# stackclock_display.net
KiCad netlist of a schematic drawn in EAGLE
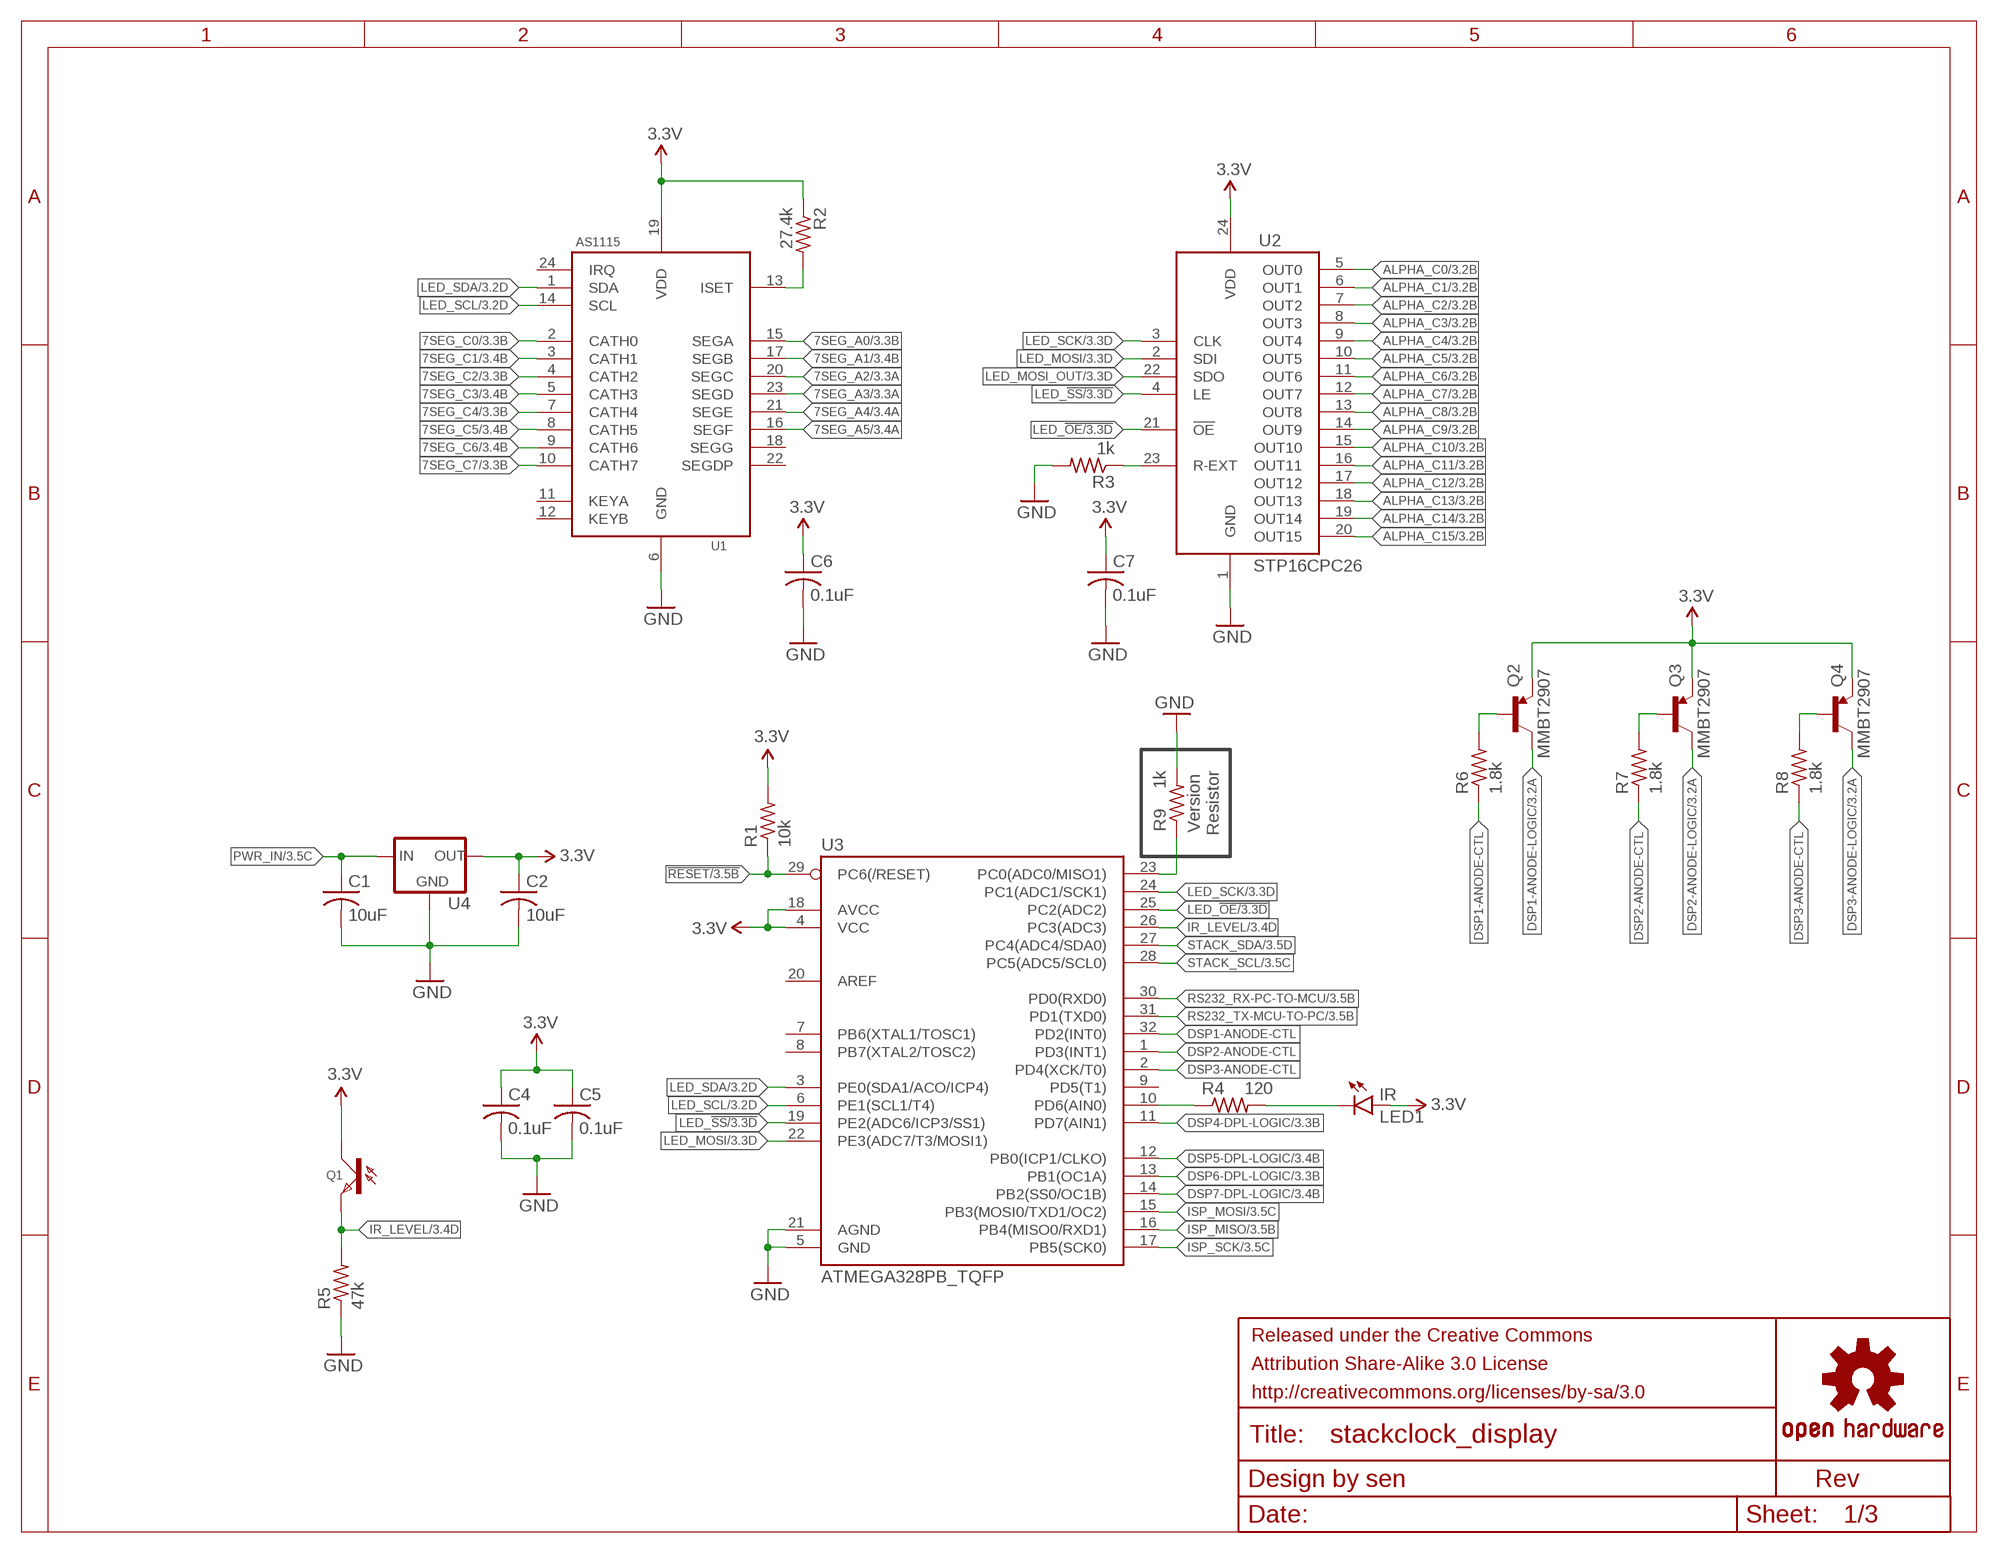
[diagram p0: schematic, sheet 1]
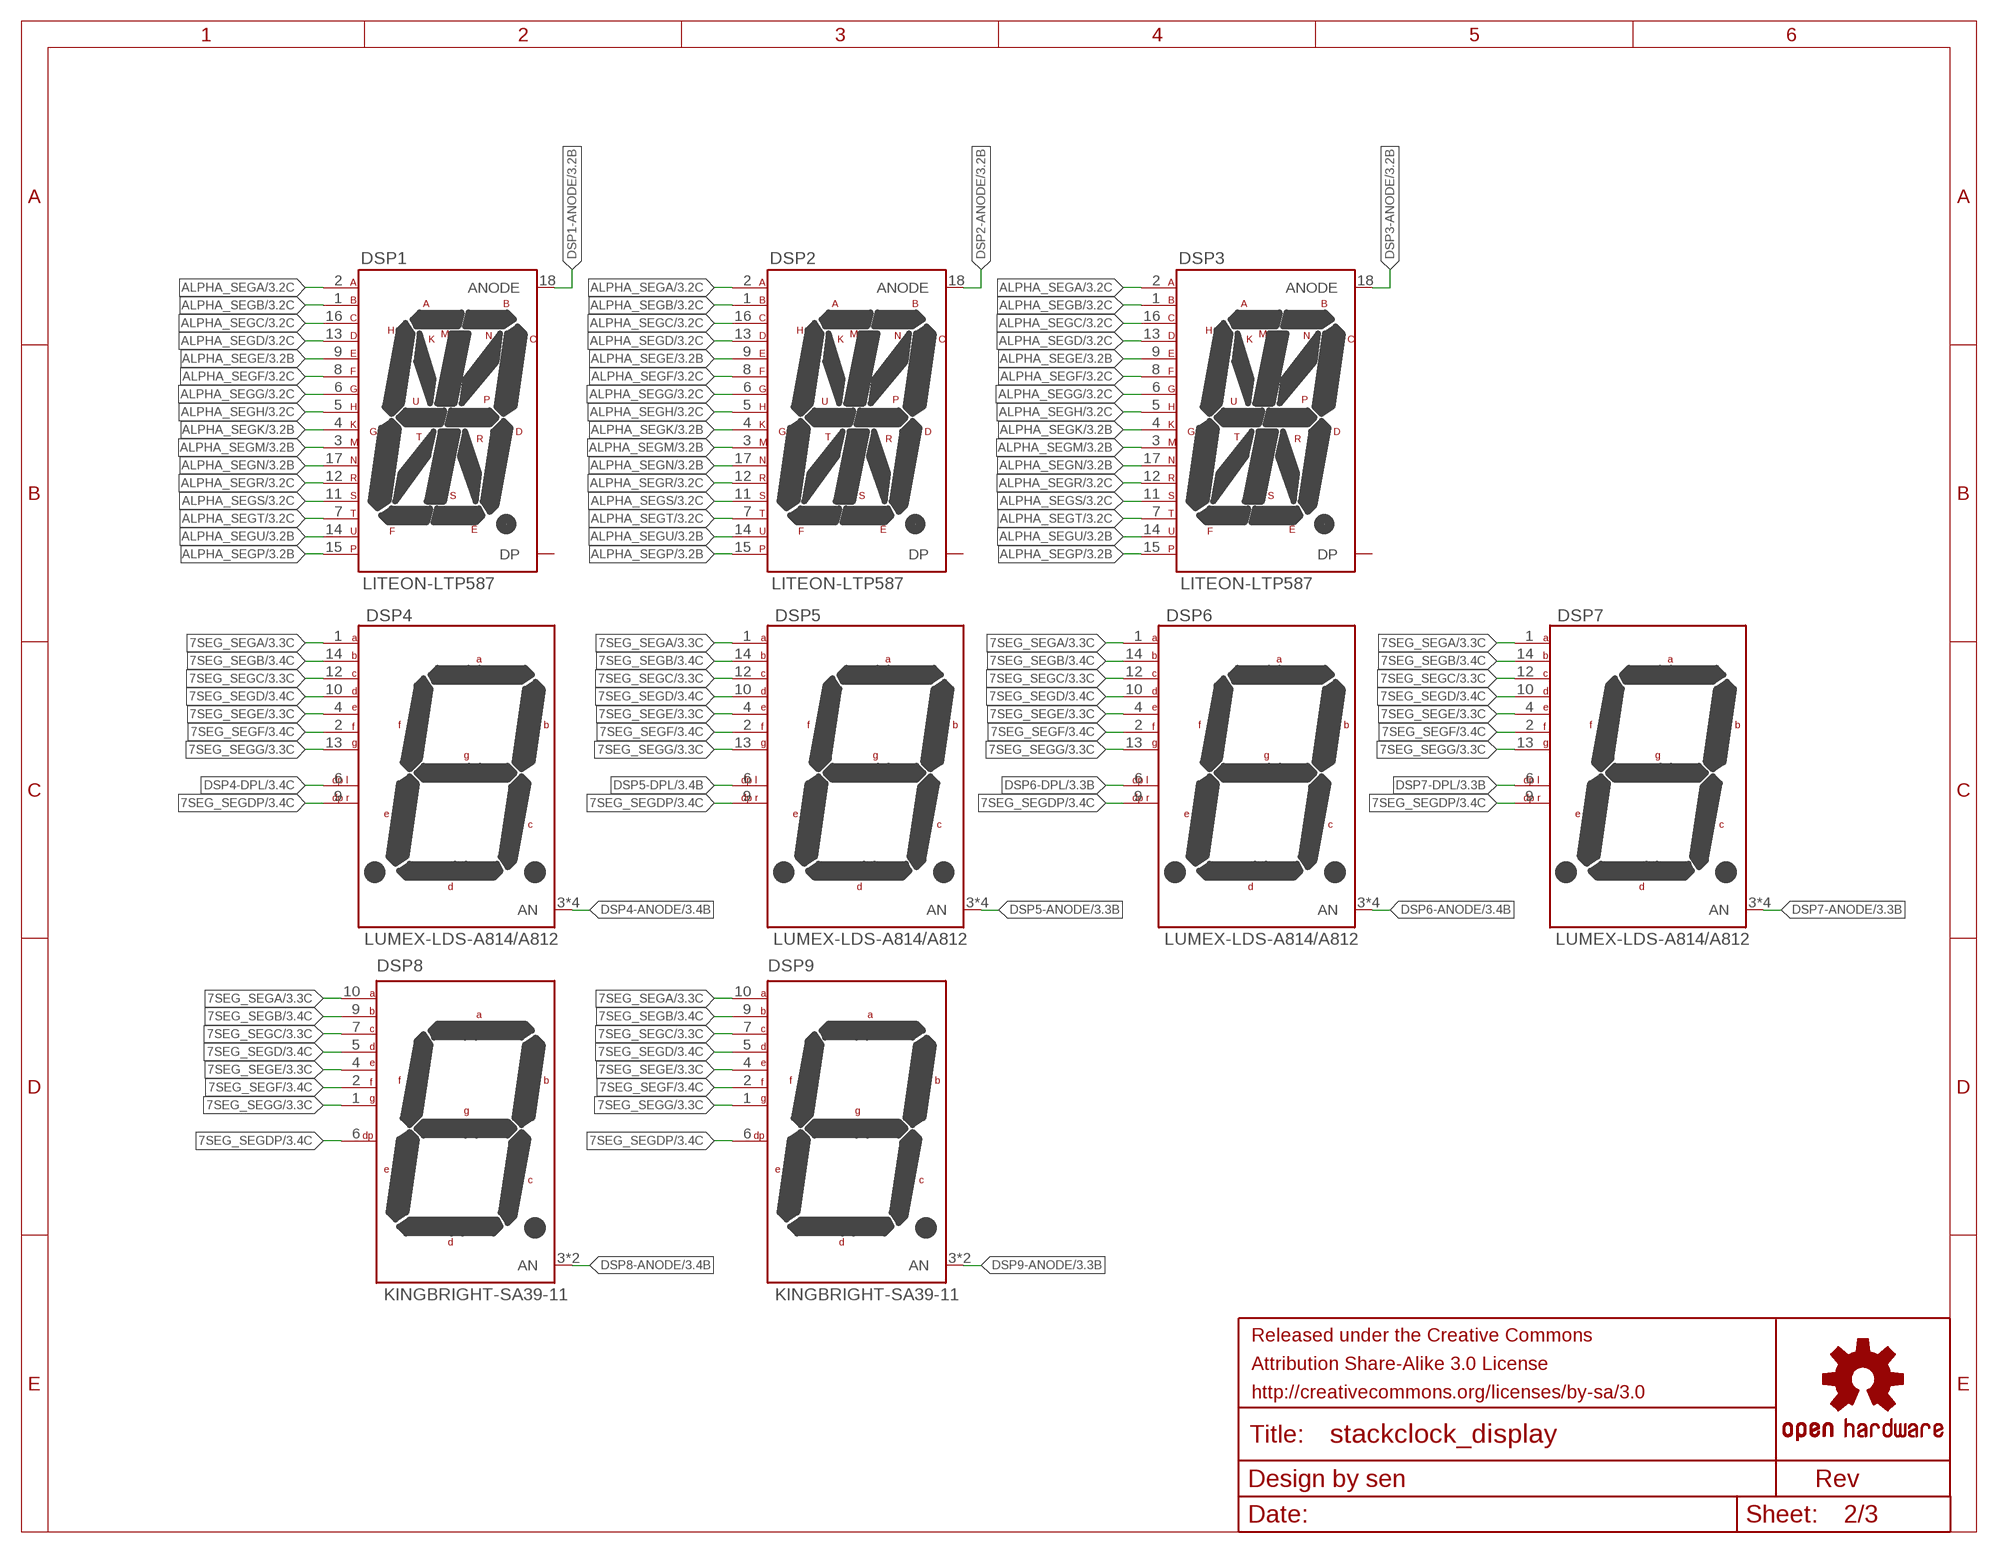
[diagram p1: schematic, sheet 2]
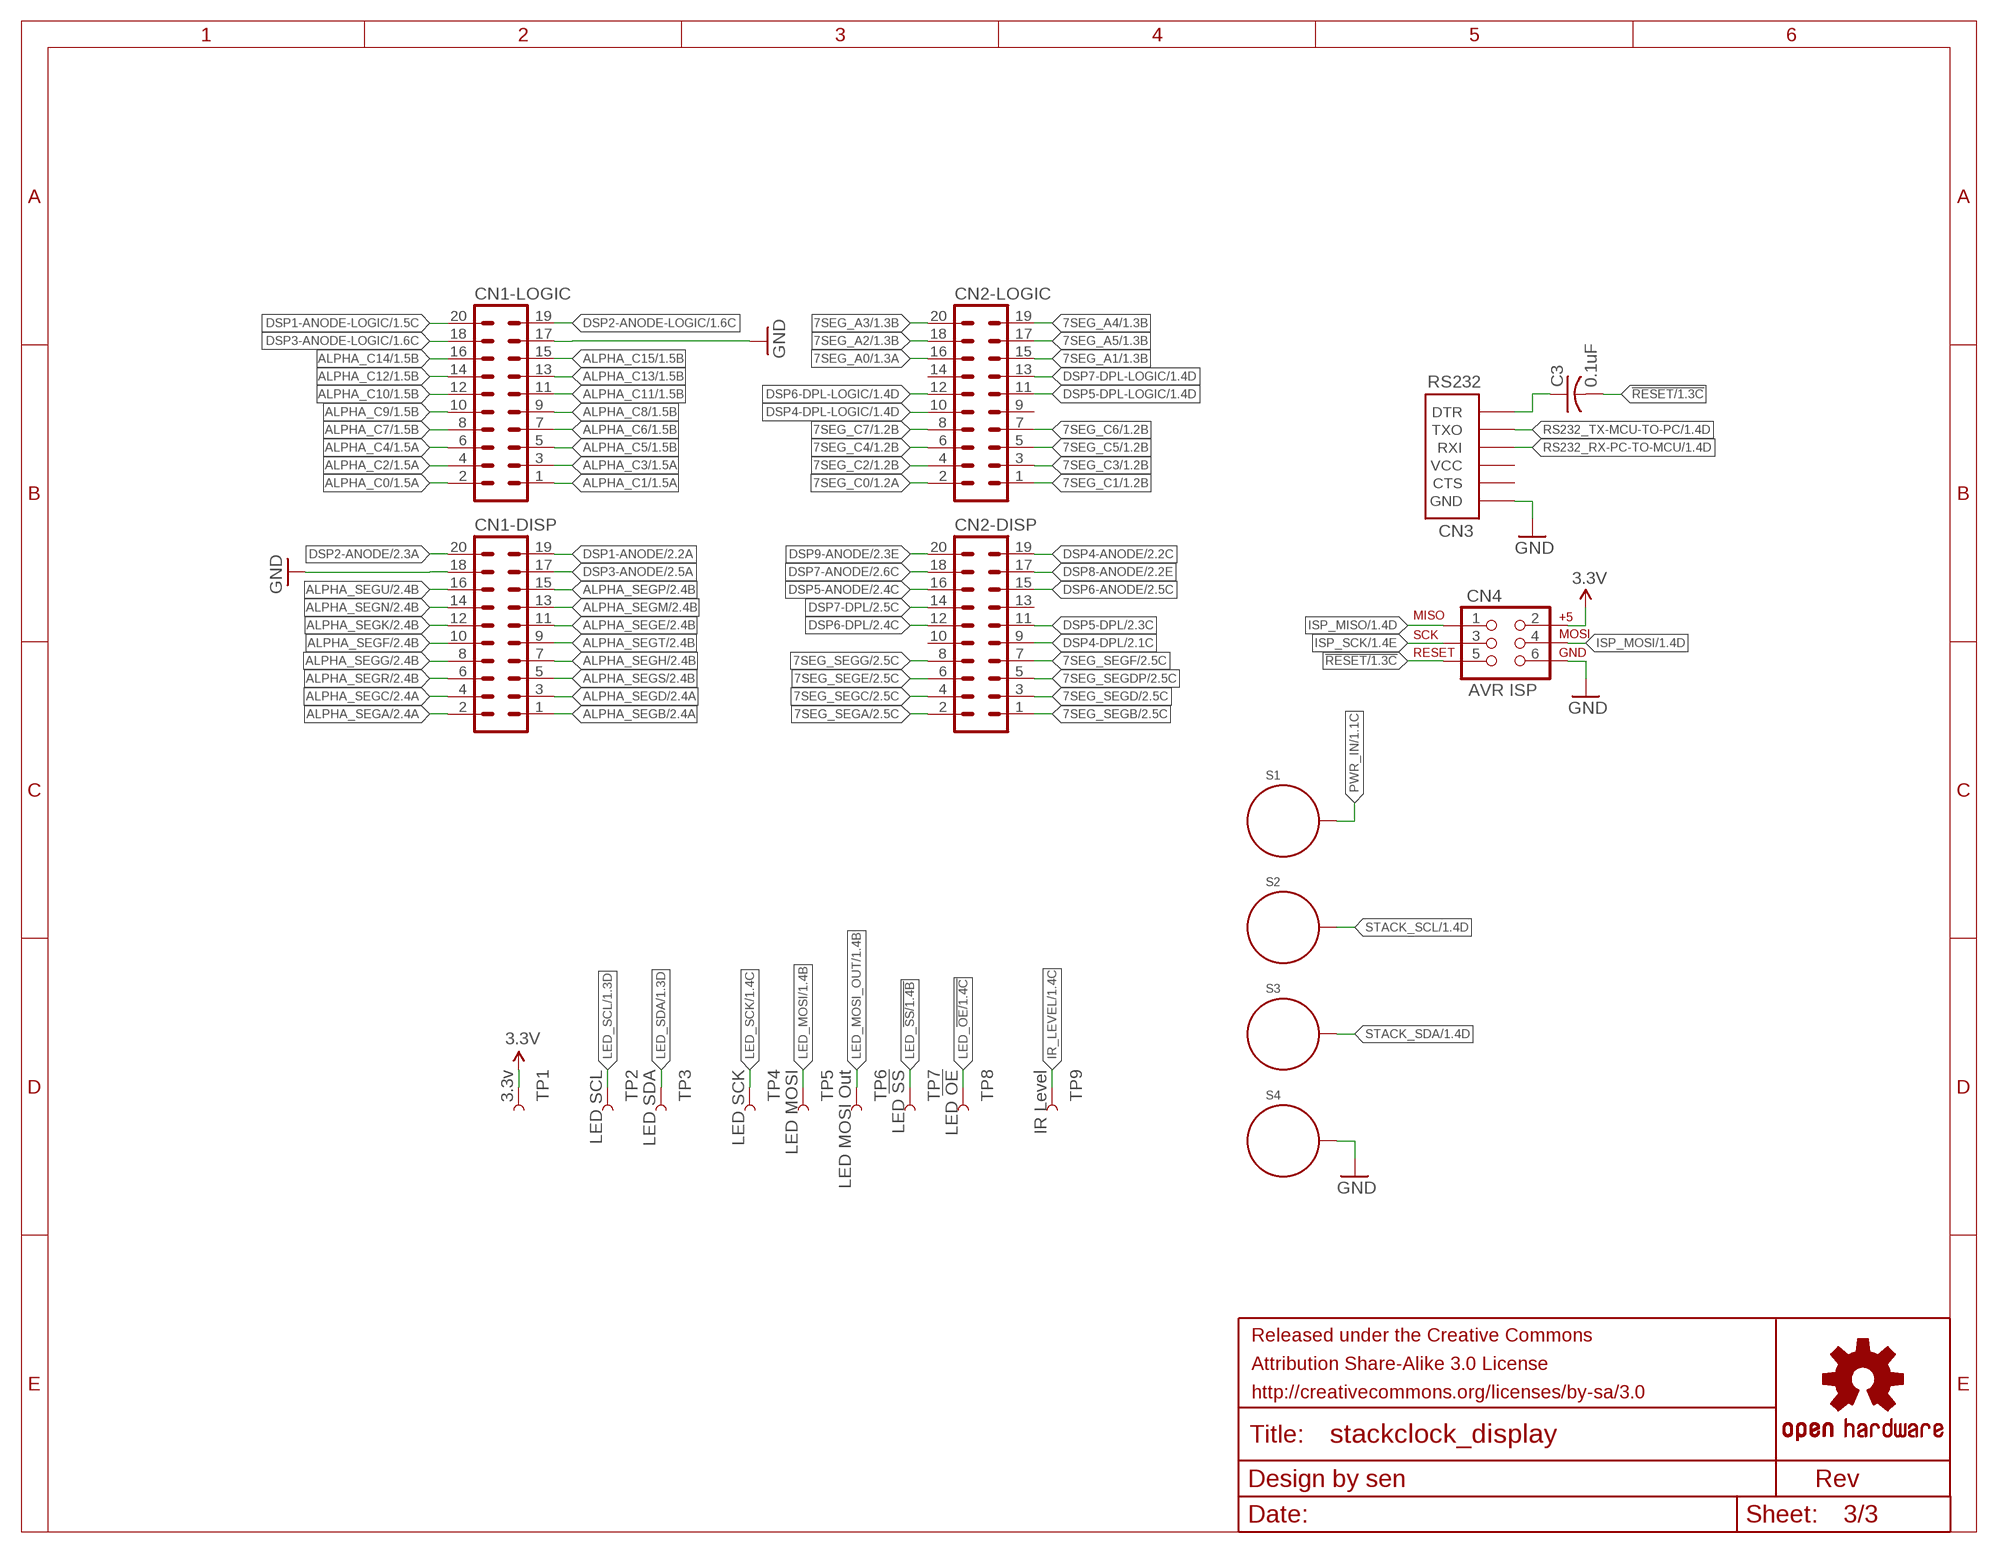
[diagram p2: schematic, sheet 3]

(export (version "E")
  (design (tool "Eeschema 10.0.6"))
  (components
    (comp (ref "DSP1")
      (value "LITEON-LTP587")
      (footprint "eagle-import:LITEON-LTP587")
      (libsource (lib "eagle-import") (part "LITEON-LTP587"))
    )
    (comp (ref "DSP2")
      (value "LITEON-LTP587")
      (footprint "eagle-import:LITEON-LTP587")
      (libsource (lib "eagle-import") (part "LITEON-LTP587"))
    )
    (comp (ref "DSP3")
      (value "LITEON-LTP587")
      (footprint "eagle-import:LITEON-LTP587")
      (libsource (lib "eagle-import") (part "LITEON-LTP587"))
    )
    (comp (ref "DSP4")
      (value "LUMEX-LDS-A814/A812")
      (footprint "eagle-import:LUMEX-LDS-A814_A812")
      (libsource (lib "eagle-import") (part "LUMEX-LDS-A814/A812"))
    )
    (comp (ref "DSP5")
      (value "LUMEX-LDS-A814/A812")
      (footprint "eagle-import:LUMEX-LDS-A814_A812")
      (libsource (lib "eagle-import") (part "LUMEX-LDS-A814/A812"))
    )
    (comp (ref "DSP6")
      (value "LUMEX-LDS-A814/A812")
      (footprint "eagle-import:LUMEX-LDS-A814_A812")
      (libsource (lib "eagle-import") (part "LUMEX-LDS-A814/A812"))
    )
    (comp (ref "DSP7")
      (value "LUMEX-LDS-A814/A812")
      (footprint "eagle-import:LUMEX-LDS-A814_A812")
      (libsource (lib "eagle-import") (part "LUMEX-LDS-A814/A812"))
    )
    (comp (ref "DSP8")
      (value "KINGBRIGHT-SA39-11")
      (footprint "eagle-import:KINGBRIGHT-SA39-11")
      (libsource (lib "eagle-import") (part "KINGBRIGHT-SA39-11"))
    )
    (comp (ref "DSP9")
      (value "KINGBRIGHT-SA39-11")
      (footprint "eagle-import:KINGBRIGHT-SA39-11")
      (libsource (lib "eagle-import") (part "KINGBRIGHT-SA39-11"))
    )
    (comp (ref "FRAME2")
      (value "FRAME-LETTER-GRID-OSHW-SENOSHW-LOGO-L")
      (footprint "eagle-import:OSHW-LOGO-L")
      (fields (field (name "REV") "002"))
      (libsource (lib "eagle-import") (part "FRAME-LETTER-GRID-OSHW-SENOSHW-LOGO-L"))
    )
    (comp (ref "C1")
      (value "10uF")
      (footprint "eagle-import:C0805")
      (libsource (lib "eagle-import") (part "C-USC0805"))
    )
    (comp (ref "C2")
      (value "10uF")
      (footprint "eagle-import:C0805")
      (libsource (lib "eagle-import") (part "C-USC0805"))
    )
    (comp (ref "C4")
      (value "0.1uF")
      (footprint "eagle-import:C0603")
      (libsource (lib "eagle-import") (part "C-USC0603"))
    )
    (comp (ref "C5")
      (value "0.1uF")
      (footprint "eagle-import:C0603")
      (libsource (lib "eagle-import") (part "C-USC0603"))
    )
    (comp (ref "C6")
      (value "0.1uF")
      (footprint "eagle-import:C0603")
      (libsource (lib "eagle-import") (part "C-USC0603"))
    )
    (comp (ref "C7")
      (value "0.1uF")
      (footprint "eagle-import:C0603")
      (libsource (lib "eagle-import") (part "C-USC0603"))
    )
    (comp (ref "FRAME1")
      (value "FRAME-LETTER-GRID-OSHW-SENOSHW-LOGO-L")
      (footprint "eagle-import:OSHW-LOGO-L")
      (fields (field (name "REV") "002"))
      (libsource (lib "eagle-import") (part "FRAME-LETTER-GRID-OSHW-SENOSHW-LOGO-L"))
    )
    (comp (ref "LED1")
      (value "IR")
      (footprint "eagle-import:LED-1206")
      (libsource (lib "eagle-import") (part "LED1206"))
    )
    (comp (ref "Q1")
      (value "PT15-21C/TR8")
      (footprint "eagle-import:1206_PHOTOTRANSISTOR")
      (libsource (lib "eagle-import") (part "PT15-21C/TR8"))
    )
    (comp (ref "Q2")
      (value "MMBT2907")
      (footprint "eagle-import:SOT23-3")
      (libsource (lib "eagle-import") (part "TRANSISTOR_PNPSMD"))
    )
    (comp (ref "Q3")
      (value "MMBT2907")
      (footprint "eagle-import:SOT23-3")
      (libsource (lib "eagle-import") (part "TRANSISTOR_PNPSMD"))
    )
    (comp (ref "Q4")
      (value "MMBT2907")
      (footprint "eagle-import:SOT23-3")
      (libsource (lib "eagle-import") (part "TRANSISTOR_PNPSMD"))
    )
    (comp (ref "R1")
      (value "10k")
      (footprint "eagle-import:R0603")
      (libsource (lib "eagle-import") (part "R-US_R0603"))
    )
    (comp (ref "R2")
      (value "27.4k")
      (footprint "eagle-import:R0603")
      (libsource (lib "eagle-import") (part "R-US_R0603"))
    )
    (comp (ref "R3")
      (value "1k")
      (footprint "eagle-import:R0603")
      (libsource (lib "eagle-import") (part "R-US_R0603"))
    )
    (comp (ref "R4")
      (value "120")
      (footprint "eagle-import:R0603")
      (libsource (lib "eagle-import") (part "R-US_R0603"))
    )
    (comp (ref "R5")
      (value "47k")
      (footprint "eagle-import:R0603")
      (libsource (lib "eagle-import") (part "R-US_R0603"))
    )
    (comp (ref "R6")
      (value "1.8k")
      (footprint "eagle-import:R0603")
      (libsource (lib "eagle-import") (part "R-US_R0603"))
    )
    (comp (ref "R7")
      (value "1.8k")
      (footprint "eagle-import:R0603")
      (libsource (lib "eagle-import") (part "R-US_R0603"))
    )
    (comp (ref "R8")
      (value "1.8k")
      (footprint "eagle-import:R0603")
      (libsource (lib "eagle-import") (part "R-US_R0603"))
    )
    (comp (ref "R9")
      (value "1k")
      (footprint "eagle-import:R0603")
      (libsource (lib "eagle-import") (part "R-US_R0603"))
    )
    (comp (ref "U1")
      (value "AS1115")
      (footprint "eagle-import:QSOP24")
      (libsource (lib "eagle-import") (part "AS1115"))
    )
    (comp (ref "U2")
      (value "STP16CPC26")
      (footprint "eagle-import:TSSOP24")
      (libsource (lib "eagle-import") (part "STP16CPC26"))
    )
    (comp (ref "U3")
      (value "ATMEGA328PB_TQFP")
      (footprint "eagle-import:TQFP32-08")
      (libsource (lib "eagle-import") (part "ATMEGA328PB_TQFP"))
    )
    (comp (ref "U4")
      (value "NCP1117DT33G")
      (footprint "eagle-import:DPAK")
      (libsource (lib "eagle-import") (part "V_REG_MC33269DT"))
    )
    (comp (ref "C3")
      (value "0.1uF")
      (footprint "eagle-import:C0603")
      (libsource (lib "eagle-import") (part "C-USC0603"))
    )
    (comp (ref "CN1-DISP")
      (value "MA10-2W")
      (footprint "eagle-import:MA10-2W")
      (libsource (lib "eagle-import") (part "MA10-2W"))
    )
    (comp (ref "CN1-LOGIC")
      (value "MA10-2")
      (footprint "eagle-import:MA10-2")
      (libsource (lib "eagle-import") (part "MA10-2"))
    )
    (comp (ref "CN2-DISP")
      (value "MA10-2W")
      (footprint "eagle-import:MA10-2W")
      (libsource (lib "eagle-import") (part "MA10-2W"))
    )
    (comp (ref "CN2-LOGIC")
      (value "MA10-2")
      (footprint "eagle-import:MA10-2")
      (libsource (lib "eagle-import") (part "MA10-2"))
    )
    (comp (ref "CN3")
      (value "RS232")
      (footprint "eagle-import:FTDI_DEVICE_SIDE")
      (libsource (lib "eagle-import") (part "FTDI_DEVICE"))
    )
    (comp (ref "CN4")
      (value "AVR ISP")
      (footprint "eagle-import:2X3_LOCK")
      (libsource (lib "eagle-import") (part "AVR_SPI_PRG_62X3_LOCK"))
    )
    (comp (ref "FRAME3")
      (value "FRAME-LETTER-GRID-OSHW-SENOSHW-LOGO-L")
      (footprint "eagle-import:OSHW-LOGO-L")
      (fields (field (name "REV") "002"))
      (libsource (lib "eagle-import") (part "FRAME-LETTER-GRID-OSHW-SENOSHW-LOGO-L"))
    )
    (comp (ref "S1")
      (value "+V")
      (footprint "eagle-import:STANDOFF-ELECTRICAL")
      (libsource (lib "eagle-import") (part "STANDOFF_ELECTRICAL"))
    )
    (comp (ref "S2")
      (value "SCL")
      (footprint "eagle-import:STANDOFF-ELECTRICAL")
      (libsource (lib "eagle-import") (part "STANDOFF_ELECTRICAL"))
    )
    (comp (ref "S3")
      (value "SDA")
      (footprint "eagle-import:STANDOFF-ELECTRICAL")
      (libsource (lib "eagle-import") (part "STANDOFF_ELECTRICAL"))
    )
    (comp (ref "S4")
      (value "GND")
      (footprint "eagle-import:STANDOFF-ELECTRICAL")
      (libsource (lib "eagle-import") (part "STANDOFF_ELECTRICAL"))
    )
    (comp (ref "TP1")
      (value "3.3v")
      (footprint "eagle-import:TP_15TH")
      (libsource (lib "eagle-import") (part "TEST-POINTTP_15TH_THRU"))
    )
    (comp (ref "TP2")
      (value "LED SCL")
      (footprint "eagle-import:TP_15TH")
      (libsource (lib "eagle-import") (part "TEST-POINTTP_15TH_THRU"))
    )
    (comp (ref "TP3")
      (value "LED SDA")
      (footprint "eagle-import:TP_15TH")
      (libsource (lib "eagle-import") (part "TEST-POINTTP_15TH_THRU"))
    )
    (comp (ref "TP4")
      (value "LED SCK")
      (footprint "eagle-import:TP_15TH")
      (libsource (lib "eagle-import") (part "TEST-POINTTP_15TH_THRU"))
    )
    (comp (ref "TP5")
      (value "LED MOSI")
      (footprint "eagle-import:TP_15TH")
      (libsource (lib "eagle-import") (part "TEST-POINTTP_15TH_THRU"))
    )
    (comp (ref "TP6")
      (value "LED MOSI Out")
      (footprint "eagle-import:TP_15TH")
      (libsource (lib "eagle-import") (part "TEST-POINTTP_15TH_THRU"))
    )
    (comp (ref "TP7")
      (value "LED !SS")
      (footprint "eagle-import:TP_15TH")
      (libsource (lib "eagle-import") (part "TEST-POINTTP_15TH_THRU"))
    )
    (comp (ref "TP8")
      (value "LED !OE")
      (footprint "eagle-import:TP_15TH")
      (libsource (lib "eagle-import") (part "TEST-POINTTP_15TH_THRU"))
    )
    (comp (ref "TP9")
      (value "IR Level")
      (footprint "eagle-import:TP_15TH")
      (libsource (lib "eagle-import") (part "TEST-POINTTP_15TH_THRU"))
    )
  )
  (nets
    (net (code "1") (name "3.3V") (class "Default")
      (node (ref "C2") (pin "1") (pinfunction "1_1") (pintype "passive"))
      (node (ref "C4") (pin "1") (pinfunction "1_1") (pintype "passive"))
      (node (ref "C5") (pin "1") (pinfunction "1_1") (pintype "passive"))
      (node (ref "C6") (pin "1") (pinfunction "1_1") (pintype "passive"))
      (node (ref "C7") (pin "1") (pinfunction "1_1") (pintype "passive"))
      (node (ref "CN4") (pin "2") (pinfunction "2_2") (pintype "passive"))
      (node (ref "LED1") (pin "A") (pinfunction "A_A") (pintype "passive"))
      (node (ref "Q1") (pin "C") (pinfunction "C_C") (pintype "passive"))
      (node (ref "Q2") (pin "2") (pinfunction "E_2") (pintype "passive"))
      (node (ref "Q3") (pin "2") (pinfunction "E_2") (pintype "passive"))
      (node (ref "Q4") (pin "2") (pinfunction "E_2") (pintype "passive"))
      (node (ref "R1") (pin "2") (pinfunction "2_2") (pintype "passive"))
      (node (ref "R2") (pin "1") (pinfunction "1_1") (pintype "passive"))
      (node (ref "TP1") (pin "P$1") (pinfunction "1_P$1") (pintype "bidirectional"))
      (node (ref "U1") (pin "19") (pinfunction "VDD_19") (pintype "power_in"))
      (node (ref "U2") (pin "24") (pinfunction "VDD_24") (pintype "bidirectional"))
      (node (ref "U3") (pin "18") (pinfunction "AVCC_18") (pintype "bidirectional"))
      (node (ref "U3") (pin "4") (pinfunction "VCC_4") (pintype "bidirectional"))
      (node (ref "U4") (pin "4") (pinfunction "OUT_4") (pintype "passive"))
    )
    (net (code "2") (name "7SEG_A0") (class "Default")
      (node (ref "CN2-LOGIC") (pin "16") (pinfunction "16_16") (pintype "passive"))
      (node (ref "U1") (pin "15") (pinfunction "SEGA_15") (pintype "output"))
    )
    (net (code "3") (name "7SEG_A1") (class "Default")
      (node (ref "CN2-LOGIC") (pin "15") (pinfunction "15_15") (pintype "passive"))
      (node (ref "U1") (pin "17") (pinfunction "SEGB_17") (pintype "output"))
    )
    (net (code "4") (name "7SEG_A2") (class "Default")
      (node (ref "CN2-LOGIC") (pin "18") (pinfunction "18_18") (pintype "passive"))
      (node (ref "U1") (pin "20") (pinfunction "SEGC_20") (pintype "output"))
    )
    (net (code "5") (name "7SEG_A3") (class "Default")
      (node (ref "CN2-LOGIC") (pin "20") (pinfunction "20_20") (pintype "passive"))
      (node (ref "U1") (pin "23") (pinfunction "SEGD_23") (pintype "output"))
    )
    (net (code "6") (name "7SEG_A4") (class "Default")
      (node (ref "CN2-LOGIC") (pin "19") (pinfunction "19_19") (pintype "passive"))
      (node (ref "U1") (pin "21") (pinfunction "SEGE_21") (pintype "output"))
    )
    (net (code "7") (name "7SEG_A5") (class "Default")
      (node (ref "CN2-LOGIC") (pin "17") (pinfunction "17_17") (pintype "passive"))
      (node (ref "U1") (pin "16") (pinfunction "SEGF_16") (pintype "output"))
    )
    (net (code "8") (name "7SEG_C0") (class "Default")
      (node (ref "CN2-LOGIC") (pin "2") (pinfunction "2_2") (pintype "passive"))
      (node (ref "U1") (pin "2") (pinfunction "CATH0_2") (pintype "output"))
    )
    (net (code "9") (name "7SEG_C1") (class "Default")
      (node (ref "CN2-LOGIC") (pin "1") (pinfunction "1_1") (pintype "passive"))
      (node (ref "U1") (pin "3") (pinfunction "CATH1_3") (pintype "output"))
    )
    (net (code "10") (name "7SEG_C2") (class "Default")
      (node (ref "CN2-LOGIC") (pin "4") (pinfunction "4_4") (pintype "passive"))
      (node (ref "U1") (pin "4") (pinfunction "CATH2_4") (pintype "output"))
    )
    (net (code "11") (name "7SEG_C3") (class "Default")
      (node (ref "CN2-LOGIC") (pin "3") (pinfunction "3_3") (pintype "passive"))
      (node (ref "U1") (pin "5") (pinfunction "CATH3_5") (pintype "output"))
    )
    (net (code "12") (name "7SEG_C4") (class "Default")
      (node (ref "CN2-LOGIC") (pin "6") (pinfunction "6_6") (pintype "passive"))
      (node (ref "U1") (pin "7") (pinfunction "CATH4_7") (pintype "output"))
    )
    (net (code "13") (name "7SEG_C5") (class "Default")
      (node (ref "CN2-LOGIC") (pin "5") (pinfunction "5_5") (pintype "passive"))
      (node (ref "U1") (pin "8") (pinfunction "CATH5_8") (pintype "output"))
    )
    (net (code "14") (name "7SEG_C6") (class "Default")
      (node (ref "CN2-LOGIC") (pin "7") (pinfunction "7_7") (pintype "passive"))
      (node (ref "U1") (pin "9") (pinfunction "CATH6_9") (pintype "output"))
    )
    (net (code "15") (name "7SEG_C7") (class "Default")
      (node (ref "CN2-LOGIC") (pin "8") (pinfunction "8_8") (pintype "passive"))
      (node (ref "U1") (pin "10") (pinfunction "CATH7_10") (pintype "output"))
    )
    (net (code "16") (name "7SEG_SEGA") (class "Default")
      (node (ref "CN2-DISP") (pin "2") (pinfunction "2_2") (pintype "passive"))
      (node (ref "DSP4") (pin "1") (pinfunction "A_1") (pintype "passive"))
      (node (ref "DSP5") (pin "1") (pinfunction "A_1") (pintype "passive"))
      (node (ref "DSP6") (pin "1") (pinfunction "A_1") (pintype "passive"))
      (node (ref "DSP7") (pin "1") (pinfunction "A_1") (pintype "passive"))
      (node (ref "DSP8") (pin "10") (pinfunction "A_10") (pintype "passive"))
      (node (ref "DSP9") (pin "10") (pinfunction "A_10") (pintype "passive"))
    )
    (net (code "17") (name "7SEG_SEGB") (class "Default")
      (node (ref "CN2-DISP") (pin "1") (pinfunction "1_1") (pintype "passive"))
      (node (ref "DSP4") (pin "14") (pinfunction "B_14") (pintype "passive"))
      (node (ref "DSP5") (pin "14") (pinfunction "B_14") (pintype "passive"))
      (node (ref "DSP6") (pin "14") (pinfunction "B_14") (pintype "passive"))
      (node (ref "DSP7") (pin "14") (pinfunction "B_14") (pintype "passive"))
      (node (ref "DSP8") (pin "9") (pinfunction "B_9") (pintype "passive"))
      (node (ref "DSP9") (pin "9") (pinfunction "B_9") (pintype "passive"))
    )
    (net (code "18") (name "7SEG_SEGC") (class "Default")
      (node (ref "CN2-DISP") (pin "4") (pinfunction "4_4") (pintype "passive"))
      (node (ref "DSP4") (pin "12") (pinfunction "C_12") (pintype "passive"))
      (node (ref "DSP5") (pin "12") (pinfunction "C_12") (pintype "passive"))
      (node (ref "DSP6") (pin "12") (pinfunction "C_12") (pintype "passive"))
      (node (ref "DSP7") (pin "12") (pinfunction "C_12") (pintype "passive"))
      (node (ref "DSP8") (pin "7") (pinfunction "C_7") (pintype "passive"))
      (node (ref "DSP9") (pin "7") (pinfunction "C_7") (pintype "passive"))
    )
    (net (code "19") (name "7SEG_SEGD") (class "Default")
      (node (ref "CN2-DISP") (pin "3") (pinfunction "3_3") (pintype "passive"))
      (node (ref "DSP4") (pin "10") (pinfunction "D_10") (pintype "passive"))
      (node (ref "DSP5") (pin "10") (pinfunction "D_10") (pintype "passive"))
      (node (ref "DSP6") (pin "10") (pinfunction "D_10") (pintype "passive"))
      (node (ref "DSP7") (pin "10") (pinfunction "D_10") (pintype "passive"))
      (node (ref "DSP8") (pin "5") (pinfunction "D_5") (pintype "passive"))
      (node (ref "DSP9") (pin "5") (pinfunction "D_5") (pintype "passive"))
    )
    (net (code "20") (name "7SEG_SEGDP") (class "Default")
      (node (ref "CN2-DISP") (pin "5") (pinfunction "5_5") (pintype "passive"))
      (node (ref "DSP4") (pin "9") (pinfunction "DP-R_9") (pintype "passive"))
      (node (ref "DSP5") (pin "9") (pinfunction "DP-R_9") (pintype "passive"))
      (node (ref "DSP6") (pin "9") (pinfunction "DP-R_9") (pintype "passive"))
      (node (ref "DSP7") (pin "9") (pinfunction "DP-R_9") (pintype "passive"))
      (node (ref "DSP8") (pin "6") (pinfunction "DP_6") (pintype "passive"))
      (node (ref "DSP9") (pin "6") (pinfunction "DP_6") (pintype "passive"))
    )
    (net (code "21") (name "7SEG_SEGE") (class "Default")
      (node (ref "CN2-DISP") (pin "6") (pinfunction "6_6") (pintype "passive"))
      (node (ref "DSP4") (pin "4") (pinfunction "E_4") (pintype "passive"))
      (node (ref "DSP5") (pin "4") (pinfunction "E_4") (pintype "passive"))
      (node (ref "DSP6") (pin "4") (pinfunction "E_4") (pintype "passive"))
      (node (ref "DSP7") (pin "4") (pinfunction "E_4") (pintype "passive"))
      (node (ref "DSP8") (pin "4") (pinfunction "E_4") (pintype "passive"))
      (node (ref "DSP9") (pin "4") (pinfunction "E_4") (pintype "passive"))
    )
    (net (code "22") (name "7SEG_SEGF") (class "Default")
      (node (ref "CN2-DISP") (pin "7") (pinfunction "7_7") (pintype "passive"))
      (node (ref "DSP4") (pin "2") (pinfunction "F_2") (pintype "passive"))
      (node (ref "DSP5") (pin "2") (pinfunction "F_2") (pintype "passive"))
      (node (ref "DSP6") (pin "2") (pinfunction "F_2") (pintype "passive"))
      (node (ref "DSP7") (pin "2") (pinfunction "F_2") (pintype "passive"))
      (node (ref "DSP8") (pin "2") (pinfunction "F_2") (pintype "passive"))
      (node (ref "DSP9") (pin "2") (pinfunction "F_2") (pintype "passive"))
    )
    (net (code "23") (name "7SEG_SEGG") (class "Default")
      (node (ref "CN2-DISP") (pin "8") (pinfunction "8_8") (pintype "passive"))
      (node (ref "DSP4") (pin "13") (pinfunction "G_13") (pintype "passive"))
      (node (ref "DSP5") (pin "13") (pinfunction "G_13") (pintype "passive"))
      (node (ref "DSP6") (pin "13") (pinfunction "G_13") (pintype "passive"))
      (node (ref "DSP7") (pin "13") (pinfunction "G_13") (pintype "passive"))
      (node (ref "DSP8") (pin "1") (pinfunction "G_1") (pintype "passive"))
      (node (ref "DSP9") (pin "1") (pinfunction "G_1") (pintype "passive"))
    )
    (net (code "24") (name "ALPHA_C0") (class "Default")
      (node (ref "CN1-LOGIC") (pin "2") (pinfunction "2_2") (pintype "passive"))
      (node (ref "U2") (pin "5") (pinfunction "OUT0_5") (pintype "output"))
    )
    (net (code "25") (name "ALPHA_C1") (class "Default")
      (node (ref "CN1-LOGIC") (pin "1") (pinfunction "1_1") (pintype "passive"))
      (node (ref "U2") (pin "6") (pinfunction "OUT1_6") (pintype "output"))
    )
    (net (code "26") (name "ALPHA_C2") (class "Default")
      (node (ref "CN1-LOGIC") (pin "4") (pinfunction "4_4") (pintype "passive"))
      (node (ref "U2") (pin "7") (pinfunction "OUT2_7") (pintype "output"))
    )
    (net (code "27") (name "ALPHA_C3") (class "Default")
      (node (ref "CN1-LOGIC") (pin "3") (pinfunction "3_3") (pintype "passive"))
      (node (ref "U2") (pin "8") (pinfunction "OUT3_8") (pintype "output"))
    )
    (net (code "28") (name "ALPHA_C4") (class "Default")
      (node (ref "CN1-LOGIC") (pin "6") (pinfunction "6_6") (pintype "passive"))
      (node (ref "U2") (pin "9") (pinfunction "OUT4_9") (pintype "output"))
    )
    (net (code "29") (name "ALPHA_C5") (class "Default")
      (node (ref "CN1-LOGIC") (pin "5") (pinfunction "5_5") (pintype "passive"))
      (node (ref "U2") (pin "10") (pinfunction "OUT5_10") (pintype "output"))
    )
    (net (code "30") (name "ALPHA_C6") (class "Default")
      (node (ref "CN1-LOGIC") (pin "7") (pinfunction "7_7") (pintype "passive"))
      (node (ref "U2") (pin "11") (pinfunction "OUT6_11") (pintype "output"))
    )
    (net (code "31") (name "ALPHA_C7") (class "Default")
      (node (ref "CN1-LOGIC") (pin "8") (pinfunction "8_8") (pintype "passive"))
      (node (ref "U2") (pin "12") (pinfunction "OUT7_12") (pintype "output"))
    )
    (net (code "32") (name "ALPHA_C8") (class "Default")
      (node (ref "CN1-LOGIC") (pin "9") (pinfunction "9_9") (pintype "passive"))
      (node (ref "U2") (pin "13") (pinfunction "OUT8_13") (pintype "output"))
    )
    (net (code "33") (name "ALPHA_C9") (class "Default")
      (node (ref "CN1-LOGIC") (pin "10") (pinfunction "10_10") (pintype "passive"))
      (node (ref "U2") (pin "14") (pinfunction "OUT9_14") (pintype "output"))
    )
    (net (code "34") (name "ALPHA_C10") (class "Default")
      (node (ref "CN1-LOGIC") (pin "12") (pinfunction "12_12") (pintype "passive"))
      (node (ref "U2") (pin "15") (pinfunction "OUT10_15") (pintype "output"))
    )
    (net (code "35") (name "ALPHA_C11") (class "Default")
      (node (ref "CN1-LOGIC") (pin "11") (pinfunction "11_11") (pintype "passive"))
      (node (ref "U2") (pin "16") (pinfunction "OUT11_16") (pintype "output"))
    )
    (net (code "36") (name "ALPHA_C12") (class "Default")
      (node (ref "CN1-LOGIC") (pin "14") (pinfunction "14_14") (pintype "passive"))
      (node (ref "U2") (pin "17") (pinfunction "OUT12_17") (pintype "output"))
    )
    (net (code "37") (name "ALPHA_C13") (class "Default")
      (node (ref "CN1-LOGIC") (pin "13") (pinfunction "13_13") (pintype "passive"))
      (node (ref "U2") (pin "18") (pinfunction "OUT13_18") (pintype "output"))
    )
    (net (code "38") (name "ALPHA_C14") (class "Default")
      (node (ref "CN1-LOGIC") (pin "16") (pinfunction "16_16") (pintype "passive"))
      (node (ref "U2") (pin "19") (pinfunction "OUT14_19") (pintype "output"))
    )
    (net (code "39") (name "ALPHA_C15") (class "Default")
      (node (ref "CN1-LOGIC") (pin "15") (pinfunction "15_15") (pintype "passive"))
      (node (ref "U2") (pin "20") (pinfunction "OUT15_20") (pintype "output"))
    )
    (net (code "40") (name "ALPHA_SEGA") (class "Default")
      (node (ref "CN1-DISP") (pin "2") (pinfunction "2_2") (pintype "passive"))
      (node (ref "DSP1") (pin "2") (pinfunction "A_2") (pintype "passive"))
      (node (ref "DSP2") (pin "2") (pinfunction "A_2") (pintype "passive"))
      (node (ref "DSP3") (pin "2") (pinfunction "A_2") (pintype "passive"))
    )
    (net (code "41") (name "ALPHA_SEGB") (class "Default")
      (node (ref "CN1-DISP") (pin "1") (pinfunction "1_1") (pintype "passive"))
      (node (ref "DSP1") (pin "1") (pinfunction "B_1") (pintype "passive"))
      (node (ref "DSP2") (pin "1") (pinfunction "B_1") (pintype "passive"))
      (node (ref "DSP3") (pin "1") (pinfunction "B_1") (pintype "passive"))
    )
    (net (code "42") (name "ALPHA_SEGC") (class "Default")
      (node (ref "CN1-DISP") (pin "4") (pinfunction "4_4") (pintype "passive"))
      (node (ref "DSP1") (pin "16") (pinfunction "C_16") (pintype "passive"))
      (node (ref "DSP2") (pin "16") (pinfunction "C_16") (pintype "passive"))
      (node (ref "DSP3") (pin "16") (pinfunction "C_16") (pintype "passive"))
    )
    (net (code "43") (name "ALPHA_SEGD") (class "Default")
      (node (ref "CN1-DISP") (pin "3") (pinfunction "3_3") (pintype "passive"))
      (node (ref "DSP1") (pin "13") (pinfunction "D_13") (pintype "passive"))
      (node (ref "DSP2") (pin "13") (pinfunction "D_13") (pintype "passive"))
      (node (ref "DSP3") (pin "13") (pinfunction "D_13") (pintype "passive"))
    )
    (net (code "44") (name "ALPHA_SEGE") (class "Default")
      (node (ref "CN1-DISP") (pin "11") (pinfunction "11_11") (pintype "passive"))
      (node (ref "DSP1") (pin "9") (pinfunction "E_9") (pintype "passive"))
      (node (ref "DSP2") (pin "9") (pinfunction "E_9") (pintype "passive"))
      (node (ref "DSP3") (pin "9") (pinfunction "E_9") (pintype "passive"))
    )
    (net (code "45") (name "ALPHA_SEGF") (class "Default")
      (node (ref "CN1-DISP") (pin "10") (pinfunction "10_10") (pintype "passive"))
      (node (ref "DSP1") (pin "8") (pinfunction "F_8") (pintype "passive"))
      (node (ref "DSP2") (pin "8") (pinfunction "F_8") (pintype "passive"))
      (node (ref "DSP3") (pin "8") (pinfunction "F_8") (pintype "passive"))
    )
    (net (code "46") (name "ALPHA_SEGG") (class "Default")
      (node (ref "CN1-DISP") (pin "8") (pinfunction "8_8") (pintype "passive"))
      (node (ref "DSP1") (pin "6") (pinfunction "G_6") (pintype "passive"))
      (node (ref "DSP2") (pin "6") (pinfunction "G_6") (pintype "passive"))
      (node (ref "DSP3") (pin "6") (pinfunction "G_6") (pintype "passive"))
    )
    (net (code "47") (name "ALPHA_SEGH") (class "Default")
      (node (ref "CN1-DISP") (pin "7") (pinfunction "7_7") (pintype "passive"))
      (node (ref "DSP1") (pin "5") (pinfunction "H_5") (pintype "passive"))
      (node (ref "DSP2") (pin "5") (pinfunction "H_5") (pintype "passive"))
      (node (ref "DSP3") (pin "5") (pinfunction "H_5") (pintype "passive"))
    )
    (net (code "48") (name "ALPHA_SEGK") (class "Default")
      (node (ref "CN1-DISP") (pin "12") (pinfunction "12_12") (pintype "passive"))
      (node (ref "DSP1") (pin "4") (pinfunction "K_4") (pintype "passive"))
      (node (ref "DSP2") (pin "4") (pinfunction "K_4") (pintype "passive"))
      (node (ref "DSP3") (pin "4") (pinfunction "K_4") (pintype "passive"))
    )
    (net (code "49") (name "ALPHA_SEGM") (class "Default")
      (node (ref "CN1-DISP") (pin "13") (pinfunction "13_13") (pintype "passive"))
      (node (ref "DSP1") (pin "3") (pinfunction "M_3") (pintype "passive"))
      (node (ref "DSP2") (pin "3") (pinfunction "M_3") (pintype "passive"))
      (node (ref "DSP3") (pin "3") (pinfunction "M_3") (pintype "passive"))
    )
    (net (code "50") (name "ALPHA_SEGN") (class "Default")
      (node (ref "CN1-DISP") (pin "14") (pinfunction "14_14") (pintype "passive"))
      (node (ref "DSP1") (pin "17") (pinfunction "N_17") (pintype "passive"))
      (node (ref "DSP2") (pin "17") (pinfunction "N_17") (pintype "passive"))
      (node (ref "DSP3") (pin "17") (pinfunction "N_17") (pintype "passive"))
    )
    (net (code "51") (name "ALPHA_SEGP") (class "Default")
      (node (ref "CN1-DISP") (pin "15") (pinfunction "15_15") (pintype "passive"))
      (node (ref "DSP1") (pin "15") (pinfunction "P_15") (pintype "passive"))
      (node (ref "DSP2") (pin "15") (pinfunction "P_15") (pintype "passive"))
      (node (ref "DSP3") (pin "15") (pinfunction "P_15") (pintype "passive"))
    )
    (net (code "52") (name "ALPHA_SEGR") (class "Default")
      (node (ref "CN1-DISP") (pin "6") (pinfunction "6_6") (pintype "passive"))
      (node (ref "DSP1") (pin "12") (pinfunction "R_12") (pintype "passive"))
      (node (ref "DSP2") (pin "12") (pinfunction "R_12") (pintype "passive"))
      (node (ref "DSP3") (pin "12") (pinfunction "R_12") (pintype "passive"))
    )
    (net (code "53") (name "ALPHA_SEGS") (class "Default")
      (node (ref "CN1-DISP") (pin "5") (pinfunction "5_5") (pintype "passive"))
      (node (ref "DSP1") (pin "11") (pinfunction "S_11") (pintype "passive"))
      (node (ref "DSP2") (pin "11") (pinfunction "S_11") (pintype "passive"))
      (node (ref "DSP3") (pin "11") (pinfunction "S_11") (pintype "passive"))
    )
    (net (code "54") (name "ALPHA_SEGT") (class "Default")
      (node (ref "CN1-DISP") (pin "9") (pinfunction "9_9") (pintype "passive"))
      (node (ref "DSP1") (pin "7") (pinfunction "T_7") (pintype "passive"))
      (node (ref "DSP2") (pin "7") (pinfunction "T_7") (pintype "passive"))
      (node (ref "DSP3") (pin "7") (pinfunction "T_7") (pintype "passive"))
    )
    (net (code "55") (name "ALPHA_SEGU") (class "Default")
      (node (ref "CN1-DISP") (pin "16") (pinfunction "16_16") (pintype "passive"))
      (node (ref "DSP1") (pin "14") (pinfunction "U_14") (pintype "passive"))
      (node (ref "DSP2") (pin "14") (pinfunction "U_14") (pintype "passive"))
      (node (ref "DSP3") (pin "14") (pinfunction "U_14") (pintype "passive"))
    )
    (net (code "56") (name "DSP1-ANODE") (class "Default")
      (node (ref "CN1-DISP") (pin "19") (pinfunction "19_19") (pintype "passive"))
      (node (ref "DSP1") (pin "18") (pinfunction "ANODE_18") (pintype "passive"))
    )
    (net (code "57") (name "DSP1-ANODE-CTL") (class "Default")
      (node (ref "R6") (pin "1") (pinfunction "1_1") (pintype "passive"))
      (node (ref "U3") (pin "32") (pinfunction "PD2(INT0)_32") (pintype "bidirectional"))
    )
    (net (code "58") (name "DSP1-ANODE-LOGIC") (class "Default")
      (node (ref "CN1-LOGIC") (pin "20") (pinfunction "20_20") (pintype "passive"))
      (node (ref "Q2") (pin "3") (pinfunction "C_3") (pintype "passive"))
    )
    (net (code "59") (name "DSP2-ANODE") (class "Default")
      (node (ref "CN1-DISP") (pin "20") (pinfunction "20_20") (pintype "passive"))
      (node (ref "DSP2") (pin "18") (pinfunction "ANODE_18") (pintype "passive"))
    )
    (net (code "60") (name "DSP2-ANODE-CTL") (class "Default")
      (node (ref "R7") (pin "1") (pinfunction "1_1") (pintype "passive"))
      (node (ref "U3") (pin "1") (pinfunction "PD3(INT1)_1") (pintype "bidirectional"))
    )
    (net (code "61") (name "DSP2-ANODE-LOGIC") (class "Default")
      (node (ref "CN1-LOGIC") (pin "19") (pinfunction "19_19") (pintype "passive"))
      (node (ref "Q3") (pin "3") (pinfunction "C_3") (pintype "passive"))
    )
    (net (code "62") (name "DSP3-ANODE") (class "Default")
      (node (ref "CN1-DISP") (pin "17") (pinfunction "17_17") (pintype "passive"))
      (node (ref "DSP3") (pin "18") (pinfunction "ANODE_18") (pintype "passive"))
    )
    (net (code "63") (name "DSP3-ANODE-CTL") (class "Default")
      (node (ref "R8") (pin "1") (pinfunction "1_1") (pintype "passive"))
      (node (ref "U3") (pin "2") (pinfunction "PD4(XCK/T0)_2") (pintype "bidirectional"))
    )
    (net (code "64") (name "DSP3-ANODE-LOGIC") (class "Default")
      (node (ref "CN1-LOGIC") (pin "18") (pinfunction "18_18") (pintype "passive"))
      (node (ref "Q4") (pin "3") (pinfunction "C_3") (pintype "passive"))
    )
    (net (code "65") (name "DSP4-ANODE") (class "Default")
      (node (ref "CN2-DISP") (pin "19") (pinfunction "19_19") (pintype "passive"))
      (node (ref "DSP4") (pin "11") (pinfunction "AN_11") (pintype "passive"))
      (node (ref "DSP4") (pin "16") (pinfunction "AN_16") (pintype "passive"))
      (node (ref "DSP4") (pin "3") (pinfunction "AN_3") (pintype "passive"))
      (node (ref "DSP4") (pin "5") (pinfunction "AN_5") (pintype "passive"))
    )
    (net (code "66") (name "DSP4-DPL") (class "Default")
      (node (ref "CN2-DISP") (pin "9") (pinfunction "9_9") (pintype "passive"))
      (node (ref "DSP4") (pin "6") (pinfunction "DP-L_6") (pintype "passive"))
    )
    (net (code "67") (name "DSP4-DPL-LOGIC") (class "Default")
      (node (ref "CN2-LOGIC") (pin "10") (pinfunction "10_10") (pintype "passive"))
      (node (ref "U3") (pin "11") (pinfunction "PD7(AIN1)_11") (pintype "bidirectional"))
    )
    (net (code "68") (name "DSP5-ANODE") (class "Default")
      (node (ref "CN2-DISP") (pin "16") (pinfunction "16_16") (pintype "passive"))
      (node (ref "DSP5") (pin "11") (pinfunction "AN_11") (pintype "passive"))
      (node (ref "DSP5") (pin "16") (pinfunction "AN_16") (pintype "passive"))
      (node (ref "DSP5") (pin "3") (pinfunction "AN_3") (pintype "passive"))
      (node (ref "DSP5") (pin "5") (pinfunction "AN_5") (pintype "passive"))
    )
    (net (code "69") (name "DSP5-DPL") (class "Default")
      (node (ref "CN2-DISP") (pin "11") (pinfunction "11_11") (pintype "passive"))
      (node (ref "DSP5") (pin "6") (pinfunction "DP-L_6") (pintype "passive"))
    )
    (net (code "70") (name "DSP5-DPL-LOGIC") (class "Default")
      (node (ref "CN2-LOGIC") (pin "11") (pinfunction "11_11") (pintype "passive"))
      (node (ref "U3") (pin "12") (pinfunction "PB0(ICP1/CLKO)_12") (pintype "bidirectional"))
    )
    (net (code "71") (name "DSP6-ANODE") (class "Default")
      (node (ref "CN2-DISP") (pin "15") (pinfunction "15_15") (pintype "passive"))
      (node (ref "DSP6") (pin "11") (pinfunction "AN_11") (pintype "passive"))
      (node (ref "DSP6") (pin "16") (pinfunction "AN_16") (pintype "passive"))
      (node (ref "DSP6") (pin "3") (pinfunction "AN_3") (pintype "passive"))
      (node (ref "DSP6") (pin "5") (pinfunction "AN_5") (pintype "passive"))
    )
    (net (code "72") (name "DSP6-DPL") (class "Default")
      (node (ref "CN2-DISP") (pin "12") (pinfunction "12_12") (pintype "passive"))
      (node (ref "DSP6") (pin "6") (pinfunction "DP-L_6") (pintype "passive"))
    )
    (net (code "73") (name "DSP6-DPL-LOGIC") (class "Default")
      (node (ref "CN2-LOGIC") (pin "12") (pinfunction "12_12") (pintype "passive"))
      (node (ref "U3") (pin "13") (pinfunction "PB1(OC1A)_13") (pintype "bidirectional"))
    )
    (net (code "74") (name "DSP7-ANODE") (class "Default")
      (node (ref "CN2-DISP") (pin "18") (pinfunction "18_18") (pintype "passive"))
      (node (ref "DSP7") (pin "11") (pinfunction "AN_11") (pintype "passive"))
      (node (ref "DSP7") (pin "16") (pinfunction "AN_16") (pintype "passive"))
      (node (ref "DSP7") (pin "3") (pinfunction "AN_3") (pintype "passive"))
      (node (ref "DSP7") (pin "5") (pinfunction "AN_5") (pintype "passive"))
    )
    (net (code "75") (name "DSP7-DPL") (class "Default")
      (node (ref "CN2-DISP") (pin "14") (pinfunction "14_14") (pintype "passive"))
      (node (ref "DSP7") (pin "6") (pinfunction "DP-L_6") (pintype "passive"))
    )
    (net (code "76") (name "DSP7-DPL-LOGIC") (class "Default")
      (node (ref "CN2-LOGIC") (pin "13") (pinfunction "13_13") (pintype "passive"))
      (node (ref "U3") (pin "14") (pinfunction "PB2(SS0/OC1B)_14") (pintype "bidirectional"))
    )
    (net (code "77") (name "DSP8-ANODE") (class "Default")
      (node (ref "CN2-DISP") (pin "17") (pinfunction "17_17") (pintype "passive"))
      (node (ref "DSP8") (pin "3") (pinfunction "AN_3") (pintype "passive"))
      (node (ref "DSP8") (pin "8") (pinfunction "AN_8") (pintype "passive"))
    )
    (net (code "78") (name "DSP9-ANODE") (class "Default")
      (node (ref "CN2-DISP") (pin "20") (pinfunction "20_20") (pintype "passive"))
      (node (ref "DSP9") (pin "3") (pinfunction "AN_3") (pintype "passive"))
      (node (ref "DSP9") (pin "8") (pinfunction "AN_8") (pintype "passive"))
    )
    (net (code "79") (name "GND") (class "Default")
      (node (ref "C1") (pin "2") (pinfunction "2_2") (pintype "passive"))
      (node (ref "C2") (pin "2") (pinfunction "2_2") (pintype "passive"))
      (node (ref "C4") (pin "2") (pinfunction "2_2") (pintype "passive"))
      (node (ref "C5") (pin "2") (pinfunction "2_2") (pintype "passive"))
      (node (ref "C6") (pin "2") (pinfunction "2_2") (pintype "passive"))
      (node (ref "C7") (pin "2") (pinfunction "2_2") (pintype "passive"))
      (node (ref "CN1-DISP") (pin "18") (pinfunction "18_18") (pintype "passive"))
      (node (ref "CN1-LOGIC") (pin "17") (pinfunction "17_17") (pintype "passive"))
      (node (ref "CN3") (pin "P$6") (pinfunction "GND_P$6") (pintype "bidirectional"))
      (node (ref "CN4") (pin "6") (pinfunction "6_6") (pintype "passive"))
      (node (ref "R3") (pin "2") (pinfunction "2_2") (pintype "passive"))
      (node (ref "R5") (pin "1") (pinfunction "1_1") (pintype "passive"))
      (node (ref "R9") (pin "2") (pinfunction "2_2") (pintype "passive"))
      (node (ref "S4") (pin "P1") (pinfunction "P$1_P1") (pintype "bidirectional"))
      (node (ref "U1") (pin "6") (pinfunction "GND_6") (pintype "power_in"))
      (node (ref "U2") (pin "1") (pinfunction "GND_1") (pintype "bidirectional"))
      (node (ref "U3") (pin "21") (pinfunction "AGND_21") (pintype "bidirectional"))
      (node (ref "U3") (pin "5") (pinfunction "GND_5") (pintype "bidirectional"))
      (node (ref "U4") (pin "1") (pinfunction "GND_1") (pintype "input"))
    )
    (net (code "80") (name "IR_LEVEL") (class "Default")
      (node (ref "Q1") (pin "E") (pinfunction "E_E") (pintype "passive"))
      (node (ref "R5") (pin "2") (pinfunction "2_2") (pintype "passive"))
      (node (ref "TP9") (pin "P$1") (pinfunction "1_P$1") (pintype "bidirectional"))
      (node (ref "U3") (pin "26") (pinfunction "PC3(ADC3)_26") (pintype "bidirectional"))
    )
    (net (code "81") (name "ISP_MISO") (class "Default")
      (node (ref "CN4") (pin "1") (pinfunction "1_1") (pintype "passive"))
      (node (ref "U3") (pin "16") (pinfunction "PB4(MISO0/RXD1)_16") (pintype "bidirectional"))
    )
    (net (code "82") (name "ISP_MOSI") (class "Default")
      (node (ref "CN4") (pin "4") (pinfunction "4_4") (pintype "passive"))
      (node (ref "U3") (pin "15") (pinfunction "PB3(MOSI0/TXD1/OC2)_15") (pintype "bidirectional"))
    )
    (net (code "83") (name "ISP_SCK") (class "Default")
      (node (ref "CN4") (pin "3") (pinfunction "3_3") (pintype "passive"))
      (node (ref "U3") (pin "17") (pinfunction "PB5(SCK0)_17") (pintype "bidirectional"))
    )
    (net (code "84") (name "LED_MOSI") (class "Default")
      (node (ref "TP5") (pin "P$1") (pinfunction "1_P$1") (pintype "bidirectional"))
      (node (ref "U2") (pin "2") (pinfunction "SDI_2") (pintype "input"))
      (node (ref "U3") (pin "22") (pinfunction "PE3(ADC7/T3/MOSI1)_22") (pintype "bidirectional"))
    )
    (net (code "85") (name "LED_MOSI_OUT") (class "Default")
      (node (ref "TP6") (pin "P$1") (pinfunction "1_P$1") (pintype "bidirectional"))
      (node (ref "U2") (pin "22") (pinfunction "SDO_22") (pintype "output"))
    )
    (net (code "86") (name "LED_SCK") (class "Default")
      (node (ref "TP4") (pin "P$1") (pinfunction "1_P$1") (pintype "bidirectional"))
      (node (ref "U2") (pin "3") (pinfunction "CLK_3") (pintype "input"))
      (node (ref "U3") (pin "24") (pinfunction "PC1(ADC1/SCK1)_24") (pintype "bidirectional"))
    )
    (net (code "87") (name "LED_SCL") (class "Default")
      (node (ref "TP2") (pin "P$1") (pinfunction "1_P$1") (pintype "bidirectional"))
      (node (ref "U1") (pin "14") (pinfunction "SCL_14") (pintype "bidirectional"))
      (node (ref "U3") (pin "6") (pinfunction "PE1(SCL1/T4)_6") (pintype "bidirectional"))
    )
    (net (code "88") (name "LED_SDA") (class "Default")
      (node (ref "TP3") (pin "P$1") (pinfunction "1_P$1") (pintype "bidirectional"))
      (node (ref "U1") (pin "1") (pinfunction "SDA_1") (pintype "bidirectional"))
      (node (ref "U3") (pin "3") (pinfunction "PE0(SDA1/ACO/ICP4)_3") (pintype "bidirectional"))
    )
    (net (code "89") (name "LED_~{OE}") (class "Default")
      (node (ref "TP8") (pin "P$1") (pinfunction "1_P$1") (pintype "bidirectional"))
      (node (ref "U2") (pin "21") (pinfunction "~{OE}_21") (pintype "input"))
      (node (ref "U3") (pin "25") (pinfunction "PC2(ADC2)_25") (pintype "bidirectional"))
    )
    (net (code "90") (name "LED_~{SS}") (class "Default")
      (node (ref "TP7") (pin "P$1") (pinfunction "1_P$1") (pintype "bidirectional"))
      (node (ref "U2") (pin "4") (pinfunction "LE_4") (pintype "input"))
      (node (ref "U3") (pin "19") (pinfunction "PE2(ADC6/ICP3/SS1)_19") (pintype "bidirectional"))
    )
    (net (code "91") (name "Net-(CN3-DTR)") (class "Default")
      (node (ref "C3") (pin "1") (pinfunction "1_1") (pintype "passive"))
      (node (ref "CN3") (pin "P$1") (pinfunction "DTR_P$1") (pintype "bidirectional"))
    )
    (net (code "92") (name "Net-(LED1-PadC)") (class "Default")
      (node (ref "LED1") (pin "C") (pinfunction "C_C") (pintype "passive"))
      (node (ref "R4") (pin "2") (pinfunction "2_2") (pintype "passive"))
    )
    (net (code "93") (name "Net-(Q2-B)") (class "Default")
      (node (ref "Q2") (pin "1") (pinfunction "B_1") (pintype "passive"))
      (node (ref "R6") (pin "2") (pinfunction "2_2") (pintype "passive"))
    )
    (net (code "94") (name "Net-(Q3-B)") (class "Default")
      (node (ref "Q3") (pin "1") (pinfunction "B_1") (pintype "passive"))
      (node (ref "R7") (pin "2") (pinfunction "2_2") (pintype "passive"))
    )
    (net (code "95") (name "Net-(Q4-B)") (class "Default")
      (node (ref "Q4") (pin "1") (pinfunction "B_1") (pintype "passive"))
      (node (ref "R8") (pin "2") (pinfunction "2_2") (pintype "passive"))
    )
    (net (code "96") (name "Net-(U1-ISET)") (class "Default")
      (node (ref "R2") (pin "2") (pinfunction "2_2") (pintype "passive"))
      (node (ref "U1") (pin "13") (pinfunction "ISET_13") (pintype "input"))
    )
    (net (code "97") (name "Net-(U2-R-EXT)") (class "Default")
      (node (ref "R3") (pin "1") (pinfunction "1_1") (pintype "passive"))
      (node (ref "U2") (pin "23") (pinfunction "R-EXT_23") (pintype "passive"))
    )
    (net (code "98") (name "Net-(U3-PC0(ADC0{slash}MISO1))") (class "Default")
      (node (ref "R9") (pin "1") (pinfunction "1_1") (pintype "passive"))
      (node (ref "U3") (pin "23") (pinfunction "PC0(ADC0/MISO1)_23") (pintype "bidirectional"))
    )
    (net (code "99") (name "Net-(U3-PD6(AIN0))") (class "Default")
      (node (ref "R4") (pin "1") (pinfunction "1_1") (pintype "passive"))
      (node (ref "U3") (pin "10") (pinfunction "PD6(AIN0)_10") (pintype "bidirectional"))
    )
    (net (code "100") (name "PWR_IN") (class "Default")
      (node (ref "C1") (pin "1") (pinfunction "1_1") (pintype "passive"))
      (node (ref "S1") (pin "P1") (pinfunction "P$1_P1") (pintype "bidirectional"))
      (node (ref "U4") (pin "3") (pinfunction "IN_3") (pintype "input"))
    )
    (net (code "101") (name "RS232_RX-PC-TO-MCU") (class "Default")
      (node (ref "CN3") (pin "P$3") (pinfunction "RXI_P$3") (pintype "bidirectional"))
      (node (ref "U3") (pin "30") (pinfunction "PD0(RXD0)_30") (pintype "bidirectional"))
    )
    (net (code "102") (name "RS232_TX-MCU-TO-PC") (class "Default")
      (node (ref "CN3") (pin "P$2") (pinfunction "TXO_P$2") (pintype "bidirectional"))
      (node (ref "U3") (pin "31") (pinfunction "PD1(TXD0)_31") (pintype "bidirectional"))
    )
    (net (code "103") (name "STACK_SCL") (class "Default")
      (node (ref "S2") (pin "P1") (pinfunction "P$1_P1") (pintype "bidirectional"))
      (node (ref "U3") (pin "28") (pinfunction "PC5(ADC5/SCL0)_28") (pintype "bidirectional"))
    )
    (net (code "104") (name "STACK_SDA") (class "Default")
      (node (ref "S3") (pin "P1") (pinfunction "P$1_P1") (pintype "bidirectional"))
      (node (ref "U3") (pin "27") (pinfunction "PC4(ADC4/SDA0)_27") (pintype "bidirectional"))
    )
    (net (code "105") (name "unconnected-(CN2-DISP-Pad10)") (class "Default")
      (node (ref "CN2-DISP") (pin "10") (pinfunction "10_10") (pintype "passive"))
    )
    (net (code "106") (name "unconnected-(CN2-DISP-Pad13)") (class "Default")
      (node (ref "CN2-DISP") (pin "13") (pinfunction "13_13") (pintype "passive"))
    )
    (net (code "107") (name "unconnected-(CN2-LOGIC-Pad9)") (class "Default")
      (node (ref "CN2-LOGIC") (pin "9") (pinfunction "9_9") (pintype "passive"))
    )
    (net (code "108") (name "unconnected-(CN2-LOGIC-Pad14)") (class "Default")
      (node (ref "CN2-LOGIC") (pin "14") (pinfunction "14_14") (pintype "passive"))
    )
    (net (code "109") (name "unconnected-(CN3-CTS-PadP$5)") (class "Default")
      (node (ref "CN3") (pin "P$5") (pinfunction "CTS_P$5") (pintype "bidirectional"))
    )
    (net (code "110") (name "unconnected-(CN3-VCC-PadP$4)") (class "Default")
      (node (ref "CN3") (pin "P$4") (pinfunction "VCC_P$4") (pintype "bidirectional"))
    )
    (net (code "111") (name "unconnected-(DSP1-DP-Pad10)") (class "Default")
      (node (ref "DSP1") (pin "10") (pinfunction "DP_10") (pintype "passive"))
    )
    (net (code "112") (name "unconnected-(DSP2-DP-Pad10)") (class "Default")
      (node (ref "DSP2") (pin "10") (pinfunction "DP_10") (pintype "passive"))
    )
    (net (code "113") (name "unconnected-(DSP3-DP-Pad10)") (class "Default")
      (node (ref "DSP3") (pin "10") (pinfunction "DP_10") (pintype "passive"))
    )
    (net (code "114") (name "unconnected-(U1-IRQ-Pad24)") (class "Default")
      (node (ref "U1") (pin "24") (pinfunction "IRQ_24") (pintype "output"))
    )
    (net (code "115") (name "unconnected-(U1-KEYA-Pad11)") (class "Default")
      (node (ref "U1") (pin "11") (pinfunction "KEYA_11") (pintype "bidirectional"))
    )
    (net (code "116") (name "unconnected-(U1-KEYB-Pad12)") (class "Default")
      (node (ref "U1") (pin "12") (pinfunction "KEYB_12") (pintype "bidirectional"))
    )
    (net (code "117") (name "unconnected-(U1-SEGDP-Pad22)") (class "Default")
      (node (ref "U1") (pin "22") (pinfunction "SEGDP_22") (pintype "output"))
    )
    (net (code "118") (name "unconnected-(U1-SEGG-Pad18)") (class "Default")
      (node (ref "U1") (pin "18") (pinfunction "SEGG_18") (pintype "output"))
    )
    (net (code "119") (name "unconnected-(U3-AREF-Pad20)") (class "Default")
      (node (ref "U3") (pin "20") (pinfunction "AREF_20") (pintype "bidirectional"))
    )
    (net (code "120") (name "unconnected-(U3-PB6(XTAL1{slash}TOSC1)-Pad7)") (class "Default")
      (node (ref "U3") (pin "7") (pinfunction "PB6(XTAL1/TOSC1)_7") (pintype "bidirectional"))
    )
    (net (code "121") (name "unconnected-(U3-PB7(XTAL2{slash}TOSC2)-Pad8)") (class "Default")
      (node (ref "U3") (pin "8") (pinfunction "PB7(XTAL2/TOSC2)_8") (pintype "bidirectional"))
    )
    (net (code "122") (name "unconnected-(U3-PD5(T1)-Pad9)") (class "Default")
      (node (ref "U3") (pin "9") (pinfunction "PD5(T1)_9") (pintype "bidirectional"))
    )
    (net (code "123") (name "~{RESET}") (class "Default")
      (node (ref "C3") (pin "2") (pinfunction "2_2") (pintype "passive"))
      (node (ref "CN4") (pin "5") (pinfunction "5_5") (pintype "passive"))
      (node (ref "R1") (pin "1") (pinfunction "1_1") (pintype "passive"))
      (node (ref "U3") (pin "29") (pinfunction "PC6(/RESET)_29") (pintype "bidirectional"))
    )
  )
)
